# Zasilanie_A4_Landscape.net
KiCad netlist of a schematic drawn in Altium Designer
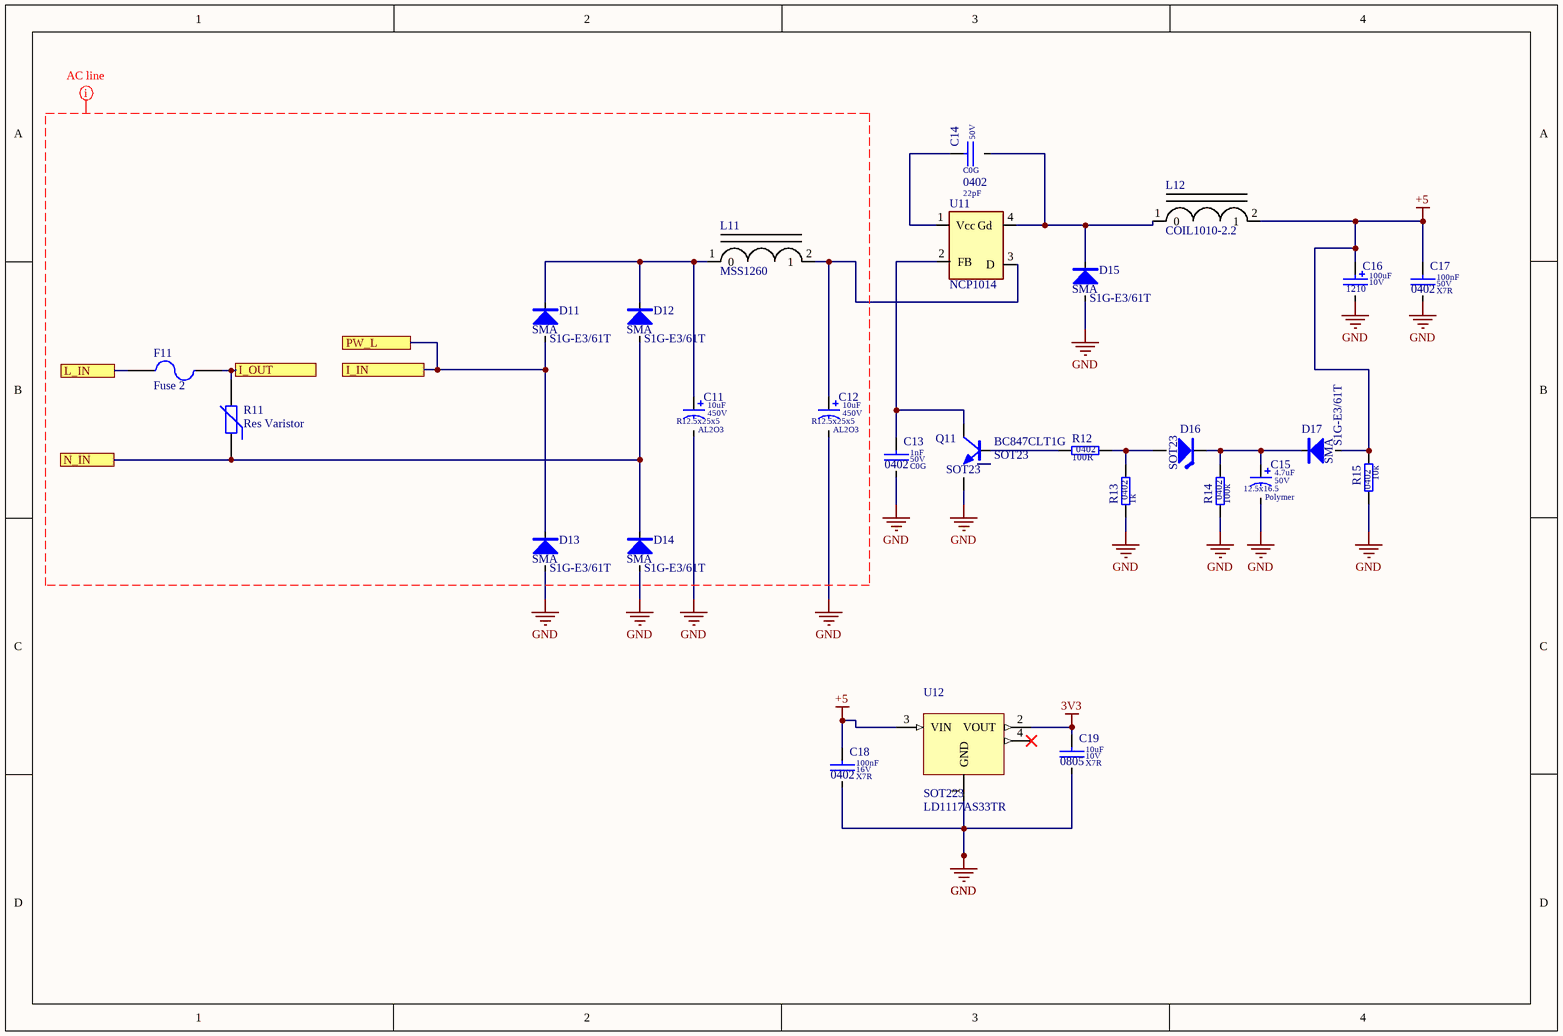
[diagram p0: Zasilanie_A4_Landscape_.SchDoc]

(export (version "E")
  (design (tool "Eeschema 10.0.6"))
  (components
    (comp (ref "C11")
      (value "10uF")
      (footprint "C_12.5x25x5")
      (description "Polarized Capacitor")
      (fields
        (field (name "DIELECTRIC") "AL2O3")
        (field (name "SCH_FOOTPRINT") "R12.5x25x5")
        (field (name "VOLTAGE") "450V")
        (field (name "PART NUMBER") "CE_15uF_450V_12.5x25x5_20")
        (field (name "MANUFACTURER") "Nichicon")
      )
      (libsource (lib "Library") (part "CE"))
    )
    (comp (ref "C12")
      (value "10uF")
      (footprint "C_12.5x25x5")
      (description "Polarized Capacitor")
      (fields
        (field (name "DIELECTRIC") "AL2O3")
        (field (name "SCH_FOOTPRINT") "R12.5x25x5")
        (field (name "VOLTAGE") "450V")
        (field (name "PART NUMBER") "CE_15uF_450V_12.5x25x5_20")
        (field (name "MANUFACTURER") "Nichicon")
      )
      (libsource (lib "Library") (part "CE"))
    )
    (comp (ref "C13")
      (value "1nF")
      (footprint "C_0402_1005")
      (description "Capacitor")
      (fields
        (field (name "DIELECTRIC") "C0G")
        (field (name "VOLTAGE") "50V")
        (field (name "SCH_FOOTPRINT") "0402")
        (field (name "PART NUMBER") "C_1nF_50V_C0G_0402_5")
        (field (name "MANUFACTURER") "Murata")
      )
      (libsource (lib "Library") (part "C"))
    )
    (comp (ref "C14")
      (value "22pF")
      (footprint "C_0402_1005")
      (description "Capacitor")
      (fields
        (field (name "DIELECTRIC") "C0G")
        (field (name "VOLTAGE") "50V")
        (field (name "SCH_FOOTPRINT") "0402")
        (field (name "PART NUMBER") "C_22pF_50V_C0G_0402_5")
        (field (name "MANUFACTURER") "AVX")
      )
      (libsource (lib "Library") (part "C"))
    )
    (comp (ref "C15")
      (value "4.7uF")
      (footprint "CE_D_12.5x16.5MM")
      (description "Polarized Capacitor")
      (fields
        (field (name "DIELECTRIC") "Polymer")
        (field (name "SCH_FOOTPRINT") "12.5x16.5")
        (field (name "VOLTAGE") "50V")
        (field (name "PART NUMBER") "CE_470uF_50V_Polymer_12.5x16.5_20")
        (field (name "MANUFACTURER") "United Chemi-Con")
      )
      (libsource (lib "Library") (part "CE"))
    )
    (comp (ref "C16")
      (value "100uF")
      (footprint "CT_1210_3225")
      (description "Capacitor")
      (fields
        (field (name "SCH_FOOTPRINT") "1210")
        (field (name "VOLTAGE") "10V")
        (field (name "PART NUMBER") "CT_100uF_10V_TA2O5_1210_20")
        (field (name "MANUFACTURER") "AVX")
      )
      (libsource (lib "Library") (part "CT"))
    )
    (comp (ref "C17")
      (value "100nF")
      (footprint "C_0402_1005")
      (description "Capacitor")
      (fields
        (field (name "DIELECTRIC") "X7R")
        (field (name "VOLTAGE") "50V")
        (field (name "SCH_FOOTPRINT") "0402")
        (field (name "PART NUMBER") "C_100nF_50V_X7R_0402_10")
        (field (name "MANUFACTURER") "Murata")
      )
      (libsource (lib "Library") (part "C"))
    )
    (comp (ref "C18")
      (value "100nF")
      (footprint "C_0402_1005")
      (description "Capacitor")
      (fields
        (field (name "DIELECTRIC") "X7R")
        (field (name "VOLTAGE") "16V")
        (field (name "SCH_FOOTPRINT") "0402")
        (field (name "PART NUMBER") "C_100nF_16V_X7R_0402_10")
        (field (name "MANUFACTURER") "Murata")
      )
      (libsource (lib "Library") (part "C"))
    )
    (comp (ref "C19")
      (value "10uF")
      (footprint "C_0805_2012")
      (description "Capacitor")
      (fields
        (field (name "DIELECTRIC") "X7R")
        (field (name "VOLTAGE") "10V")
        (field (name "SCH_FOOTPRINT") "0805")
        (field (name "PART NUMBER") "C_10uF_10V_X7R_0805_10")
        (field (name "MANUFACTURER") "Samsung Electro-Mechanics")
      )
      (libsource (lib "Library") (part "C"))
    )
    (comp (ref "D11")
      (value "S1G-E3/61T")
      (footprint "SMA_DO-214AC")
      (fields
        (field (name "SCH_FOOTPRINT") "SMA")
        (field (name "PART NUMBER") "D_S1GE3/61T_1A_400V_SMA")
        (field (name "VOLTAGE") "400V")
        (field (name "MANUFACTURER") "Vishay")
      )
      (libsource (lib "Library") (part "D"))
    )
    (comp (ref "D12")
      (value "S1G-E3/61T")
      (footprint "SMA_DO-214AC")
      (fields
        (field (name "SCH_FOOTPRINT") "SMA")
        (field (name "PART NUMBER") "D_S1GE3/61T_1A_400V_SMA")
        (field (name "VOLTAGE") "400V")
        (field (name "MANUFACTURER") "Vishay")
      )
      (libsource (lib "Library") (part "D"))
    )
    (comp (ref "D13")
      (value "S1G-E3/61T")
      (footprint "SMA_DO-214AC")
      (fields
        (field (name "SCH_FOOTPRINT") "SMA")
        (field (name "PART NUMBER") "D_S1GE3/61T_1A_400V_SMA")
        (field (name "VOLTAGE") "400V")
        (field (name "MANUFACTURER") "Vishay")
      )
      (libsource (lib "Library") (part "D"))
    )
    (comp (ref "D14")
      (value "S1G-E3/61T")
      (footprint "SMA_DO-214AC")
      (fields
        (field (name "SCH_FOOTPRINT") "SMA")
        (field (name "PART NUMBER") "D_S1GE3/61T_1A_400V_SMA")
        (field (name "VOLTAGE") "400V")
        (field (name "MANUFACTURER") "Vishay")
      )
      (libsource (lib "Library") (part "D"))
    )
    (comp (ref "D15")
      (value "S1G-E3/61T")
      (footprint "SMA_DO-214AC")
      (fields
        (field (name "SCH_FOOTPRINT") "SMA")
        (field (name "PART NUMBER") "D_S1GE3/61T_1A_400V_SMA")
        (field (name "VOLTAGE") "400V")
        (field (name "MANUFACTURER") "Vishay")
      )
      (libsource (lib "Library") (part "D"))
    )
    (comp (ref "D16")
      (value "BZX84-C3V9")
      (footprint "D_SOT23_TO236_SC59")
      (description "Zener")
      (fields
        (field (name "SCH_FOOTPRINT") "SOT23")
        (field (name "PART NUMBER") "DZ_3V9-SOT23")
        (field (name "VOLTAGE") "3.9V")
      )
      (libsource (lib "Library") (part "DZ"))
    )
    (comp (ref "D17")
      (value "S1G-E3/61T")
      (footprint "SMA_DO-214AC")
      (fields
        (field (name "SCH_FOOTPRINT") "SMA")
        (field (name "PART NUMBER") "D_S1GE3/61T_1A_400V_SMA")
        (field (name "VOLTAGE") "400V")
        (field (name "MANUFACTURER") "Vishay")
      )
      (libsource (lib "Library") (part "D"))
    )
    (comp (ref "F11")
      (value "Fuse 2")
      (footprint "PIN-W2/E2.8")
      (description "Fuse")
      (fields (field (name "PUBLISHER") "Altium Limited"))
      (libsource (lib "Miscellaneous Devices") (part "Fuse 2"))
    )
    (comp (ref "L11")
      (value "MSS1260")
      (footprint "MSS1260")
      (libsource (lib "Integrated_Library1") (part "MSS1260"))
    )
    (comp (ref "L12")
      (value "COIL1010-2.2")
      (footprint "COIL1010-2.2")
      (libsource (lib "Integrated_Library1") (part "COIL1010-2.2"))
    )
    (comp (ref "Q11")
      (value "BC847CLT1G")
      (footprint "SOT23_TO236_SC59")
      (fields
        (field (name "PART NUMBER") "QNP_BC847C_45V_0A1")
        (field (name "SCH_FOOTPRINT") "SOT23")
        (field (name "VOLTAGE") "45V")
        (field (name "MANUFACTURER") "ON Semiconductor")
      )
      (libsource (lib "Library") (part "QNP_BEC"))
    )
    (comp (ref "R11")
      (value "Res Varistor")
      (footprint "6-0805_N")
      (description "Varistor (Voltage-Sensitive Resistor)")
      (fields (field (name "PUBLISHER") "Altium Limited"))
      (libsource (lib "Miscellaneous Devices") (part "Res Varistor"))
    )
    (comp (ref "R12")
      (value "100R")
      (footprint "R_0402_1005")
      (fields
        (field (name "SCH_FOOTPRINT") "0402")
        (field (name "PART NUMBER") "R_100R_0402_1")
        (field (name "VOLTAGE") "50V")
        (field (name "POWER") "63mW")
      )
      (libsource (lib "Library") (part "R"))
    )
    (comp (ref "R13")
      (value "1k")
      (footprint "R_0402_1005")
      (fields
        (field (name "SCH_FOOTPRINT") "0402")
        (field (name "PART NUMBER") "R_1k_0402")
        (field (name "VOLTAGE") "50V")
        (field (name "POWER") "63mW")
      )
      (libsource (lib "Library") (part "R"))
    )
    (comp (ref "R14")
      (value "100k")
      (footprint "R_0402_1005")
      (fields
        (field (name "SCH_FOOTPRINT") "0402")
        (field (name "PART NUMBER") "R_100k_0402_1")
        (field (name "VOLTAGE") "50V")
        (field (name "POWER") "63mW")
      )
      (libsource (lib "Library") (part "R"))
    )
    (comp (ref "R15")
      (value "10k")
      (footprint "R_0402_1005")
      (fields
        (field (name "SCH_FOOTPRINT") "0402")
        (field (name "PART NUMBER") "R_10k_0402_1")
        (field (name "VOLTAGE") "50V")
        (field (name "POWER") "63mW")
      )
      (libsource (lib "Library") (part "R"))
    )
    (comp (ref "U11")
      (value "NCP1014")
      (footprint "NCP1014_SOT-223")
      (libsource (lib "Integrated_Library1") (part "NCP1014"))
    )
    (comp (ref "U12")
      (value "LD1117AS33TR")
      (footprint "SOT223_SC73")
      (description "Low-Dropout Positive Voltage Regulator")
      (fields
        (field (name "PART NUMBER") "VL_LD1117AS33TR_3V3_1A2")
        (field (name "SCH_FOOTPRINT") "SOT223")
        (field (name "VOLTAGE") "3.3V")
      )
      (libsource (lib "Library") (part "VL_LD1117AS33TR_3V3_1A2"))
    )
  )
  (nets
    (net (code "1") (name "+5") (class "Default")
      (node (ref "C16") (pin "1") (pinfunction "1_1") (pintype "passive"))
      (node (ref "C17") (pin "1") (pinfunction "1_1") (pintype "passive"))
      (node (ref "C18") (pin "1") (pinfunction "1_1") (pintype "passive"))
      (node (ref "D17") (pin "2") (pintype "passive"))
      (node (ref "L12") (pin "2") (pinfunction "1_2") (pintype "passive"))
      (node (ref "R15") (pin "1") (pinfunction "1_1") (pintype "passive"))
      (node (ref "U12") (pin "3") (pinfunction "VIN_3") (pintype "input"))
    )
    (net (code "2") (name "/I_IN") (class "Default")
      (node (ref "D11") (pin "2") (pintype "passive"))
      (node (ref "D13") (pin "1") (pintype "passive"))
    )
    (net (code "3") (name "/I_OUT") (class "Default")
      (node (ref "F11") (pin "2") (pinfunction "2_2") (pintype "passive"))
      (node (ref "R11") (pin "2") (pinfunction "2_2") (pintype "passive"))
    )
    (net (code "4") (name "/L_IN") (class "Default")
      (node (ref "F11") (pin "1") (pinfunction "1_1") (pintype "passive"))
    )
    (net (code "5") (name "/N_IN") (class "Default")
      (node (ref "D12") (pin "2") (pintype "passive"))
      (node (ref "D14") (pin "1") (pintype "passive"))
      (node (ref "R11") (pin "1") (pinfunction "1_1") (pintype "passive"))
    )
    (net (code "6") (name "3V3") (class "Default")
      (node (ref "C19") (pin "1") (pinfunction "1_1") (pintype "passive"))
      (node (ref "U12") (pin "2") (pinfunction "VOUT_2") (pintype "output"))
    )
    (net (code "7") (name "GND") (class "Default")
      (node (ref "C11") (pin "2") (pinfunction "2_2") (pintype "passive"))
      (node (ref "C12") (pin "2") (pinfunction "2_2") (pintype "passive"))
      (node (ref "C13") (pin "2") (pinfunction "2_2") (pintype "passive"))
      (node (ref "C15") (pin "2") (pinfunction "2_2") (pintype "passive"))
      (node (ref "C16") (pin "2") (pinfunction "2_2") (pintype "passive"))
      (node (ref "C17") (pin "2") (pinfunction "2_2") (pintype "passive"))
      (node (ref "C18") (pin "2") (pinfunction "2_2") (pintype "passive"))
      (node (ref "C19") (pin "2") (pinfunction "2_2") (pintype "passive"))
      (node (ref "D13") (pin "2") (pintype "passive"))
      (node (ref "D14") (pin "2") (pintype "passive"))
      (node (ref "D15") (pin "2") (pintype "passive"))
      (node (ref "Q11") (pin "2") (pinfunction "E_2") (pintype "passive"))
      (node (ref "R13") (pin "1") (pinfunction "1_1") (pintype "passive"))
      (node (ref "R14") (pin "1") (pinfunction "1_1") (pintype "passive"))
      (node (ref "R15") (pin "2") (pinfunction "2_2") (pintype "passive"))
      (node (ref "U12") (pin "1") (pinfunction "GND_1") (pintype "power_in"))
    )
    (net (code "8") (name "Net-(D16-A)") (class "Default")
      (node (ref "D16") (pin "2") (pinfunction "A_2") (pintype "passive"))
      (node (ref "R12") (pin "2") (pinfunction "2_2") (pintype "passive"))
      (node (ref "R13") (pin "2") (pinfunction "2_2") (pintype "passive"))
    )
    (net (code "9") (name "Net-(D16-K)") (class "Default")
      (node (ref "C15") (pin "1") (pinfunction "1_1") (pintype "passive"))
      (node (ref "D16") (pin "1") (pinfunction "K_1") (pintype "passive"))
      (node (ref "D17") (pin "1") (pintype "passive"))
      (node (ref "R14") (pin "2") (pinfunction "2_2") (pintype "passive"))
    )
    (net (code "10") (name "Net-(L11-0)") (class "Default")
      (node (ref "C11") (pin "1") (pinfunction "1_1") (pintype "passive"))
      (node (ref "D11") (pin "1") (pintype "passive"))
      (node (ref "D12") (pin "1") (pintype "passive"))
      (node (ref "L11") (pin "1") (pinfunction "0_1") (pintype "passive"))
    )
    (net (code "11") (name "Net-(L11-1)") (class "Default")
      (node (ref "C12") (pin "1") (pinfunction "1_1") (pintype "passive"))
      (node (ref "L11") (pin "2") (pinfunction "1_2") (pintype "passive"))
      (node (ref "U11") (pin "3") (pinfunction "D_3") (pintype "passive"))
    )
    (net (code "12") (name "Net-(L12-0)") (class "Default")
      (node (ref "C14") (pin "2") (pinfunction "2_2") (pintype "passive"))
      (node (ref "D15") (pin "1") (pintype "passive"))
      (node (ref "L12") (pin "1") (pinfunction "0_1") (pintype "passive"))
      (node (ref "U11") (pin "4") (pinfunction "Gd_4") (pintype "passive"))
    )
    (net (code "13") (name "Net-(Q11-B)") (class "Default")
      (node (ref "Q11") (pin "1") (pinfunction "B_1") (pintype "passive"))
      (node (ref "R12") (pin "1") (pinfunction "1_1") (pintype "passive"))
    )
    (net (code "14") (name "Net-(Q11-C)") (class "Default")
      (node (ref "C13") (pin "1") (pinfunction "1_1") (pintype "passive"))
      (node (ref "Q11") (pin "3") (pinfunction "C_3") (pintype "passive"))
      (node (ref "U11") (pin "2") (pinfunction "FB_2") (pintype "passive"))
    )
    (net (code "15") (name "Net-(U11-Vcc)") (class "Default")
      (node (ref "C14") (pin "1") (pinfunction "1_1") (pintype "passive"))
      (node (ref "U11") (pin "1") (pinfunction "Vcc_1") (pintype "passive"))
    )
    (net (code "16") (name "unconnected-(U12-VOUT-Pad4)") (class "Default")
      (node (ref "U12") (pin "4") (pinfunction "VOUT_4") (pintype "output+no_connect"))
    )
  )
)
